# Gator_Air.net
KiCad netlist of a schematic drawn in EAGLE
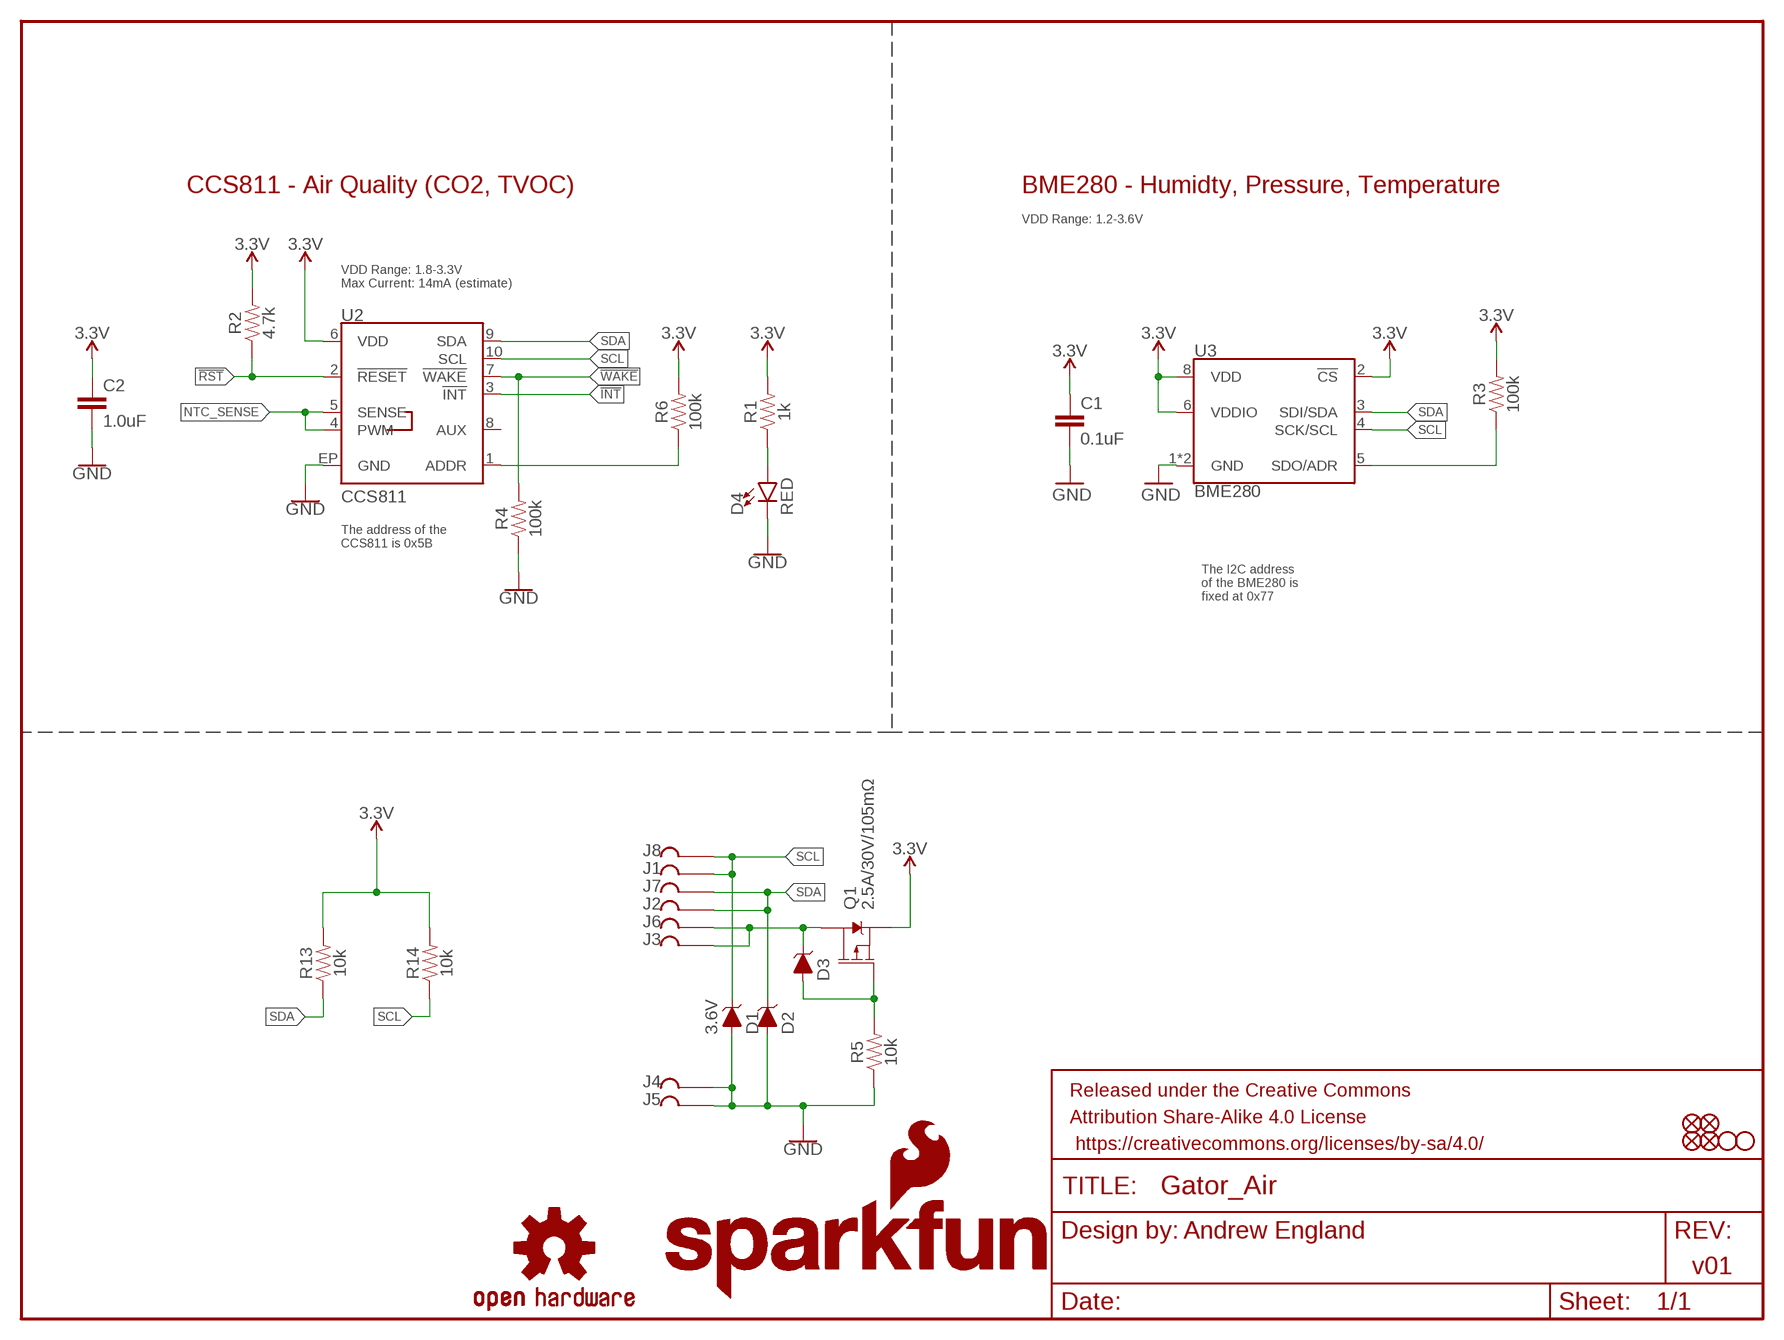
[diagram p0: schematic, sheet 1]

(export (version "E")
  (design (tool "Eeschema 10.0.6"))
  (components
    (comp (ref "C1")
      (value "0.1uF")
      (footprint "eagle-import:0603")
      (libsource (lib "eagle-import") (part "0.1UF-0603-25V-(+80/-20%)"))
    )
    (comp (ref "C2")
      (value "1.0uF")
      (footprint "eagle-import:0603")
      (libsource (lib "eagle-import") (part "1.0UF-0603-16V-10%"))
    )
    (comp (ref "D1")
      (value "3.6V")
      (footprint "eagle-import:SOD-323")
      (libsource (lib "eagle-import") (part "DIODE-ZENER-BZT52C3V6S"))
    )
    (comp (ref "D2")
      (value "3.6V")
      (footprint "eagle-import:SOD-323")
      (libsource (lib "eagle-import") (part "DIODE-ZENER-BZT52C3V6S"))
    )
    (comp (ref "D3")
      (value "3.6V")
      (footprint "eagle-import:SOD-323")
      (libsource (lib "eagle-import") (part "DIODE-ZENER-BZT52C3V6S"))
    )
    (comp (ref "D4")
      (value "RED")
      (footprint "eagle-import:LED-0603")
      (libsource (lib "eagle-import") (part "LED-RED0603"))
    )
    (comp (ref "FD1")
      (value "FIDUCIAL1X2")
      (footprint "eagle-import:FIDUCIAL-1X2")
      (libsource (lib "eagle-import") (part "FIDUCIAL1X2"))
    )
    (comp (ref "FD2")
      (value "FIDUCIAL1X2")
      (footprint "eagle-import:FIDUCIAL-1X2")
      (libsource (lib "eagle-import") (part "FIDUCIAL1X2"))
    )
    (comp (ref "FD3")
      (value "FIDUCIAL1X2")
      (footprint "eagle-import:FIDUCIAL-1X2")
      (libsource (lib "eagle-import") (part "FIDUCIAL1X2"))
    )
    (comp (ref "FD4")
      (value "FIDUCIAL1X2")
      (footprint "eagle-import:FIDUCIAL-1X2")
      (libsource (lib "eagle-import") (part "FIDUCIAL1X2"))
    )
    (comp (ref "FRAME1")
      (value "FRAME-LETTER")
      (footprint "eagle-import:CREATIVE_COMMONS")
      (libsource (lib "eagle-import") (part "FRAME-LETTER"))
    )
    (comp (ref "H2")
      (value "STAND-OFF")
      (footprint "eagle-import:STAND-OFF")
      (libsource (lib "eagle-import") (part "STAND-OFF"))
    )
    (comp (ref "H4")
      (value "STAND-OFF")
      (footprint "eagle-import:STAND-OFF")
      (libsource (lib "eagle-import") (part "STAND-OFF"))
    )
    (comp (ref "J1")
      (value "GATORGATOR_MINI")
      (footprint "eagle-import:GATOR_MINI")
      (libsource (lib "eagle-import") (part "GATORGATOR_MINI"))
    )
    (comp (ref "J2")
      (value "GATORGATOR_MINI")
      (footprint "eagle-import:GATOR_MINI")
      (libsource (lib "eagle-import") (part "GATORGATOR_MINI"))
    )
    (comp (ref "J3")
      (value "GATORGATOR_MINI")
      (footprint "eagle-import:GATOR_MINI")
      (libsource (lib "eagle-import") (part "GATORGATOR_MINI"))
    )
    (comp (ref "J4")
      (value "GATORGATOR_MINI")
      (footprint "eagle-import:GATOR_MINI")
      (libsource (lib "eagle-import") (part "GATORGATOR_MINI"))
    )
    (comp (ref "J5")
      (value "GATORGATOR_MINI")
      (footprint "eagle-import:GATOR_MINI")
      (libsource (lib "eagle-import") (part "GATORGATOR_MINI"))
    )
    (comp (ref "J6")
      (value "GATORGATOR_MINI")
      (footprint "eagle-import:GATOR_MINI")
      (libsource (lib "eagle-import") (part "GATORGATOR_MINI"))
    )
    (comp (ref "J7")
      (value "GATORGATOR_MINI")
      (footprint "eagle-import:GATOR_MINI")
      (libsource (lib "eagle-import") (part "GATORGATOR_MINI"))
    )
    (comp (ref "J8")
      (value "GATORGATOR_MINI")
      (footprint "eagle-import:GATOR_MINI")
      (libsource (lib "eagle-import") (part "GATORGATOR_MINI"))
    )
    (comp (ref "LOGO1")
      (value "SFE_LOGO_NAME.1_INCH")
      (footprint "eagle-import:SFE_LOGO_NAME_.1")
      (libsource (lib "eagle-import") (part "SFE_LOGO_NAME.1_INCH"))
    )
    (comp (ref "LOGO2")
      (value "SFE_LOGO_NAME_FLAME.1_INCH")
      (footprint "eagle-import:SFE_LOGO_NAME_FLAME_.1")
      (libsource (lib "eagle-import") (part "SFE_LOGO_NAME_FLAME.1_INCH"))
    )
    (comp (ref "LOGO4")
      (value "OSHW-LOGOS")
      (footprint "eagle-import:OSHW-LOGO-S")
      (libsource (lib "eagle-import") (part "OSHW-LOGOS"))
    )
    (comp (ref "Q1")
      (value "2.5A/30V/105mΩ")
      (footprint "eagle-import:SOT23-3")
      (libsource (lib "eagle-import") (part "MOSFET_PCH-DMG2307L"))
    )
    (comp (ref "R1")
      (value "1k")
      (footprint "eagle-import:0603")
      (libsource (lib "eagle-import") (part "1KOHM-0603-1/10W-1%"))
    )
    (comp (ref "R2")
      (value "4.7k")
      (footprint "eagle-import:0603")
      (libsource (lib "eagle-import") (part "4.7KOHM-0603-1/10W-1%"))
    )
    (comp (ref "R3")
      (value "100k")
      (footprint "eagle-import:0603")
      (libsource (lib "eagle-import") (part "100KOHM-0603-1/10W-1%"))
    )
    (comp (ref "R4")
      (value "100k")
      (footprint "eagle-import:0603")
      (libsource (lib "eagle-import") (part "100KOHM-0603-1/10W-1%"))
    )
    (comp (ref "R5")
      (value "10k")
      (footprint "eagle-import:0603")
      (libsource (lib "eagle-import") (part "10KOHM-0603-1/10W-1%"))
    )
    (comp (ref "R6")
      (value "100k")
      (footprint "eagle-import:0603")
      (libsource (lib "eagle-import") (part "100KOHM-0603-1/10W-1%"))
    )
    (comp (ref "R13")
      (value "10k")
      (footprint "eagle-import:0603")
      (libsource (lib "eagle-import") (part "10KOHM-0603-1/10W-1%"))
    )
    (comp (ref "R14")
      (value "10k")
      (footprint "eagle-import:0603")
      (libsource (lib "eagle-import") (part "10KOHM-0603-1/10W-1%"))
    )
    (comp (ref "U2")
      (value "CCS811")
      (footprint "eagle-import:LGA10")
      (libsource (lib "eagle-import") (part "CCS811PRODUCTION"))
    )
    (comp (ref "U3")
      (value "BME280")
      (footprint "eagle-import:LGA-8-2.5X2.5")
      (libsource (lib "eagle-import") (part "BME280"))
    )
  )
  (nets
    (net (code "1") (name "/~{INT}") (class "Default")
      (node (ref "U2") (pin "3") (pinfunction "~{INT}_3") (pintype "bidirectional"))
    )
    (net (code "2") (name "/~{RST}") (class "Default")
      (node (ref "R2") (pin "1") (pinfunction "1_1") (pintype "passive"))
      (node (ref "U2") (pin "2") (pinfunction "~{RESET}_2") (pintype "bidirectional"))
    )
    (net (code "3") (name "/~{WAKE}") (class "Default")
      (node (ref "R4") (pin "2") (pinfunction "2_2") (pintype "passive"))
      (node (ref "U2") (pin "7") (pinfunction "~{WAKE}_7") (pintype "bidirectional"))
    )
    (net (code "4") (name "3.3V") (class "Default")
      (node (ref "C1") (pin "1") (pinfunction "1_1") (pintype "passive"))
      (node (ref "C2") (pin "1") (pinfunction "1_1") (pintype "passive"))
      (node (ref "Q1") (pin "2") (pinfunction "S_2") (pintype "bidirectional"))
      (node (ref "R1") (pin "2") (pinfunction "2_2") (pintype "passive"))
      (node (ref "R13") (pin "2") (pinfunction "2_2") (pintype "passive"))
      (node (ref "R14") (pin "2") (pinfunction "2_2") (pintype "passive"))
      (node (ref "R2") (pin "2") (pinfunction "2_2") (pintype "passive"))
      (node (ref "R3") (pin "2") (pinfunction "2_2") (pintype "passive"))
      (node (ref "R6") (pin "2") (pinfunction "2_2") (pintype "passive"))
      (node (ref "U2") (pin "6") (pinfunction "VDD_6") (pintype "bidirectional"))
      (node (ref "U3") (pin "2") (pinfunction "~{CS}_2") (pintype "bidirectional"))
      (node (ref "U3") (pin "6") (pinfunction "VDDIO_6") (pintype "bidirectional"))
      (node (ref "U3") (pin "8") (pinfunction "VDD_8") (pintype "bidirectional"))
    )
    (net (code "5") (name "GND") (class "Default")
      (node (ref "C1") (pin "2") (pinfunction "2_2") (pintype "passive"))
      (node (ref "C2") (pin "2") (pinfunction "2_2") (pintype "passive"))
      (node (ref "D1") (pin "A") (pinfunction "A_A") (pintype "passive"))
      (node (ref "D2") (pin "A") (pinfunction "A_A") (pintype "passive"))
      (node (ref "D4") (pin "C") (pinfunction "C_C") (pintype "passive"))
      (node (ref "J4") (pin "P$2") (pinfunction "P$1_P$2") (pintype "bidirectional"))
      (node (ref "J5") (pin "P$2") (pinfunction "P$1_P$2") (pintype "bidirectional"))
      (node (ref "R4") (pin "1") (pinfunction "1_1") (pintype "passive"))
      (node (ref "R5") (pin "1") (pinfunction "1_1") (pintype "passive"))
      (node (ref "U2") (pin "EP") (pinfunction "GND_EP") (pintype "bidirectional"))
      (node (ref "U3") (pin "1") (pinfunction "GND_1") (pintype "bidirectional"))
      (node (ref "U3") (pin "7") (pinfunction "GND_7") (pintype "bidirectional"))
    )
    (net (code "6") (name "NTC_SENSE") (class "Default")
      (node (ref "U2") (pin "4") (pinfunction "PWM_4") (pintype "bidirectional"))
      (node (ref "U2") (pin "5") (pinfunction "SENSE_5") (pintype "bidirectional"))
    )
    (net (code "7") (name "Net-(D4-PadA)") (class "Default")
      (node (ref "D4") (pin "A") (pinfunction "A_A") (pintype "passive"))
      (node (ref "R1") (pin "1") (pinfunction "1_1") (pintype "passive"))
    )
    (net (code "8") (name "Net-(J3-P$1)") (class "Default")
      (node (ref "D3") (pin "C") (pinfunction "C_C") (pintype "passive"))
      (node (ref "J3") (pin "P$2") (pinfunction "P$1_P$2") (pintype "bidirectional"))
      (node (ref "J6") (pin "P$2") (pinfunction "P$1_P$2") (pintype "bidirectional"))
      (node (ref "Q1") (pin "3") (pinfunction "D_3") (pintype "bidirectional"))
    )
    (net (code "9") (name "Net-(Q1-G)") (class "Default")
      (node (ref "D3") (pin "A") (pinfunction "A_A") (pintype "passive"))
      (node (ref "Q1") (pin "1") (pinfunction "G_1") (pintype "bidirectional"))
      (node (ref "R5") (pin "2") (pinfunction "2_2") (pintype "passive"))
    )
    (net (code "10") (name "Net-(U2-ADDR)") (class "Default")
      (node (ref "R6") (pin "1") (pinfunction "1_1") (pintype "passive"))
      (node (ref "U2") (pin "1") (pinfunction "ADDR_1") (pintype "bidirectional"))
    )
    (net (code "11") (name "Net-(U3-SDO{slash}ADR)") (class "Default")
      (node (ref "R3") (pin "1") (pinfunction "1_1") (pintype "passive"))
      (node (ref "U3") (pin "5") (pinfunction "SDO/ADR_5") (pintype "bidirectional"))
    )
    (net (code "12") (name "SCL") (class "Default")
      (node (ref "D1") (pin "C") (pinfunction "C_C") (pintype "passive"))
      (node (ref "J1") (pin "P$2") (pinfunction "P$1_P$2") (pintype "bidirectional"))
      (node (ref "J8") (pin "P$2") (pinfunction "P$1_P$2") (pintype "bidirectional"))
      (node (ref "R14") (pin "1") (pinfunction "1_1") (pintype "passive"))
      (node (ref "U2") (pin "10") (pinfunction "SCL_10") (pintype "bidirectional"))
      (node (ref "U3") (pin "4") (pinfunction "SCK/SCL_4") (pintype "bidirectional"))
    )
    (net (code "13") (name "SDA") (class "Default")
      (node (ref "D2") (pin "C") (pinfunction "C_C") (pintype "passive"))
      (node (ref "J2") (pin "P$2") (pinfunction "P$1_P$2") (pintype "bidirectional"))
      (node (ref "J7") (pin "P$2") (pinfunction "P$1_P$2") (pintype "bidirectional"))
      (node (ref "R13") (pin "1") (pinfunction "1_1") (pintype "passive"))
      (node (ref "U2") (pin "9") (pinfunction "SDA_9") (pintype "bidirectional"))
      (node (ref "U3") (pin "3") (pinfunction "SDI/SDA_3") (pintype "bidirectional"))
    )
    (net (code "14") (name "unconnected-(U2-AUX-Pad8)") (class "Default")
      (node (ref "U2") (pin "8") (pinfunction "AUX_8") (pintype "bidirectional"))
    )
  )
)
